# controller.net
KiCad netlist of a schematic drawn in EAGLE
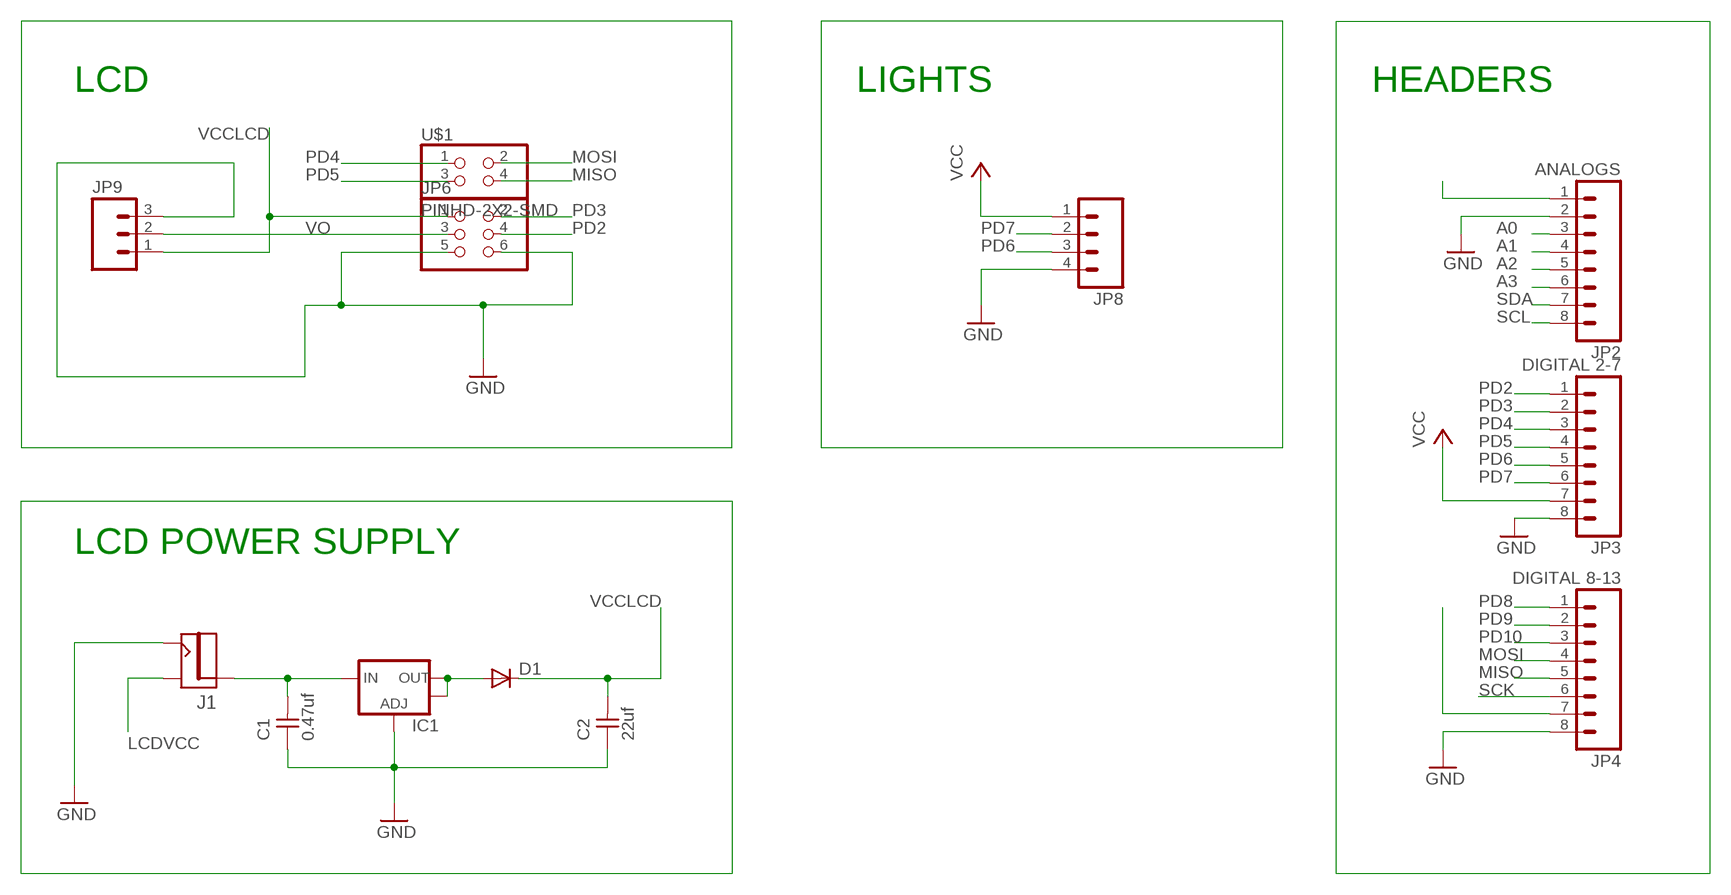
[diagram p0: schematic, sheet 1]

(export (version "E")
  (design (tool "Eeschema 10.0.6"))
  (components
    (comp (ref "C1")
      (value "0.47uf")
      (footprint "eagle-import:1206")
      (libsource (lib "eagle-import") (part "UNPOLARIZED_CAPACITOR1206"))
    )
    (comp (ref "C2")
      (value "22uf")
      (footprint "eagle-import:1206")
      (libsource (lib "eagle-import") (part "UNPOLARIZED_CAPACITOR1206"))
    )
    (comp (ref "D1")
      (value "DIODESOD123")
      (footprint "eagle-import:SOD123")
      (libsource (lib "eagle-import") (part "DIODESOD123"))
    )
    (comp (ref "IC1")
      (value "V_REG_LM1117SOT223")
      (footprint "eagle-import:SOT223")
      (libsource (lib "eagle-import") (part "V_REG_LM1117SOT223"))
    )
    (comp (ref "J1")
      (value "JACK.65MM")
      (footprint "eagle-import:JACK_.65MM")
      (libsource (lib "eagle-import") (part "JACK.65MM"))
    )
    (comp (ref "JP2")
      (value "ANALOGS")
      (footprint "eagle-import:1X08")
      (libsource (lib "eagle-import") (part "M08"))
    )
    (comp (ref "JP3")
      (value "DIGITAL 2-7")
      (footprint "eagle-import:1X08")
      (libsource (lib "eagle-import") (part "M08"))
    )
    (comp (ref "JP4")
      (value "DIGITAL 8-13")
      (footprint "eagle-import:1X08")
      (libsource (lib "eagle-import") (part "M08"))
    )
    (comp (ref "JP6")
      (value "PINHD-2X3-SMD")
      (footprint "eagle-import:2X03SMD")
      (libsource (lib "eagle-import") (part "PINHD-2X3-SMD"))
    )
    (comp (ref "JP8")
      (value "M04PTH")
      (footprint "eagle-import:1X04")
      (libsource (lib "eagle-import") (part "M04PTH"))
    )
    (comp (ref "JP9")
      (value "M03PTH")
      (footprint "eagle-import:1X03")
      (libsource (lib "eagle-import") (part "M03PTH"))
    )
    (comp (ref "U$1")
      (value "PINHD-2X2-SMD")
      (footprint "eagle-import:2X02SMD")
      (libsource (lib "eagle-import") (part "PINHD-2X2-SMD"))
    )
  )
  (nets
    (net (code "1") (name "/A0") (class "Default")
      (node (ref "JP2") (pin "3") (pinfunction "3_3") (pintype "passive"))
    )
    (net (code "2") (name "/A1") (class "Default")
      (node (ref "JP2") (pin "4") (pinfunction "4_4") (pintype "passive"))
    )
    (net (code "3") (name "/A2") (class "Default")
      (node (ref "JP2") (pin "5") (pinfunction "5_5") (pintype "passive"))
    )
    (net (code "4") (name "/A3") (class "Default")
      (node (ref "JP2") (pin "6") (pinfunction "6_6") (pintype "passive"))
    )
    (net (code "5") (name "/LCDVCC") (class "Default")
      (node (ref "J1") (pin "CONTACT") (pinfunction "SHUNT_CONTACT") (pintype "bidirectional"))
    )
    (net (code "6") (name "/MISO") (class "Default")
      (node (ref "JP4") (pin "5") (pinfunction "5_5") (pintype "passive"))
      (node (ref "U$1") (pin "4") (pinfunction "4_4") (pintype "passive"))
    )
    (net (code "7") (name "/MOSI") (class "Default")
      (node (ref "JP4") (pin "4") (pinfunction "4_4") (pintype "passive"))
      (node (ref "U$1") (pin "2") (pinfunction "2_2") (pintype "passive"))
    )
    (net (code "8") (name "/PD2") (class "Default")
      (node (ref "JP3") (pin "1") (pinfunction "1_1") (pintype "passive"))
      (node (ref "JP6") (pin "4") (pinfunction "4_4") (pintype "passive"))
    )
    (net (code "9") (name "/PD3") (class "Default")
      (node (ref "JP3") (pin "2") (pinfunction "2_2") (pintype "passive"))
      (node (ref "JP6") (pin "2") (pinfunction "2_2") (pintype "passive"))
    )
    (net (code "10") (name "/PD4") (class "Default")
      (node (ref "JP3") (pin "3") (pinfunction "3_3") (pintype "passive"))
      (node (ref "U$1") (pin "1") (pinfunction "1_1") (pintype "passive"))
    )
    (net (code "11") (name "/PD5") (class "Default")
      (node (ref "JP3") (pin "4") (pinfunction "4_4") (pintype "passive"))
      (node (ref "U$1") (pin "3") (pinfunction "3_3") (pintype "passive"))
    )
    (net (code "12") (name "/PD6") (class "Default")
      (node (ref "JP3") (pin "5") (pinfunction "5_5") (pintype "passive"))
      (node (ref "JP8") (pin "3") (pinfunction "3_3") (pintype "passive"))
    )
    (net (code "13") (name "/PD7") (class "Default")
      (node (ref "JP3") (pin "6") (pinfunction "6_6") (pintype "passive"))
      (node (ref "JP8") (pin "2") (pinfunction "2_2") (pintype "passive"))
    )
    (net (code "14") (name "/PD8") (class "Default")
      (node (ref "JP4") (pin "1") (pinfunction "1_1") (pintype "passive"))
    )
    (net (code "15") (name "/PD9") (class "Default")
      (node (ref "JP4") (pin "2") (pinfunction "2_2") (pintype "passive"))
    )
    (net (code "16") (name "/PD10") (class "Default")
      (node (ref "JP4") (pin "3") (pinfunction "3_3") (pintype "passive"))
    )
    (net (code "17") (name "/SCK") (class "Default")
      (node (ref "JP4") (pin "6") (pinfunction "6_6") (pintype "passive"))
    )
    (net (code "18") (name "/SCL") (class "Default")
      (node (ref "JP2") (pin "8") (pinfunction "8_8") (pintype "passive"))
    )
    (net (code "19") (name "/SDA") (class "Default")
      (node (ref "JP2") (pin "7") (pinfunction "7_7") (pintype "passive"))
    )
    (net (code "20") (name "/VCCLCD") (class "Default")
      (node (ref "C2") (pin "2") (pinfunction "2_2") (pintype "passive"))
      (node (ref "D1") (pin "CATHODE") (pinfunction "C_CATHODE") (pintype "passive"))
      (node (ref "JP6") (pin "1") (pinfunction "1_1") (pintype "passive"))
      (node (ref "JP9") (pin "1") (pinfunction "1_1") (pintype "passive"))
    )
    (net (code "21") (name "/VO") (class "Default")
      (node (ref "JP6") (pin "3") (pinfunction "3_3") (pintype "passive"))
      (node (ref "JP9") (pin "2") (pinfunction "2_2") (pintype "passive"))
    )
    (net (code "22") (name "GND") (class "Default")
      (node (ref "C1") (pin "1") (pinfunction "1_1") (pintype "passive"))
      (node (ref "C2") (pin "1") (pinfunction "1_1") (pintype "passive"))
      (node (ref "IC1") (pin "1") (pinfunction "ADJ_1") (pintype "input"))
      (node (ref "J1") (pin "SHUNT") (pinfunction "CONTACT_SHUNT") (pintype "bidirectional"))
      (node (ref "JP2") (pin "2") (pinfunction "2_2") (pintype "passive"))
      (node (ref "JP3") (pin "8") (pinfunction "8_8") (pintype "passive"))
      (node (ref "JP4") (pin "8") (pinfunction "8_8") (pintype "passive"))
      (node (ref "JP6") (pin "5") (pinfunction "5_5") (pintype "passive"))
      (node (ref "JP6") (pin "6") (pinfunction "6_6") (pintype "passive"))
      (node (ref "JP8") (pin "4") (pinfunction "4_4") (pintype "passive"))
      (node (ref "JP9") (pin "3") (pinfunction "3_3") (pintype "passive"))
    )
    (net (code "23") (name "Net-(D1-A)") (class "Default")
      (node (ref "D1") (pin "ANODE") (pinfunction "A_ANODE") (pintype "passive"))
      (node (ref "IC1") (pin "2") (pinfunction "OUT_2") (pintype "output"))
      (node (ref "IC1") (pin "4") (pinfunction "OUT_4") (pintype "output"))
    )
    (net (code "24") (name "Net-(IC1-IN)") (class "Default")
      (node (ref "C1") (pin "2") (pinfunction "2_2") (pintype "passive"))
      (node (ref "IC1") (pin "3") (pinfunction "IN_3") (pintype "input"))
      (node (ref "J1") (pin "PIN") (pinfunction "PIN_PIN") (pintype "bidirectional"))
    )
    (net (code "25") (name "VCC") (class "Default")
      (node (ref "JP3") (pin "7") (pinfunction "7_7") (pintype "passive"))
      (node (ref "JP8") (pin "1") (pinfunction "1_1") (pintype "passive"))
    )
    (net (code "26") (name "unconnected-(JP2-Pad1)") (class "Default")
      (node (ref "JP2") (pin "1") (pinfunction "1_1") (pintype "passive"))
    )
    (net (code "27") (name "unconnected-(JP4-Pad7)") (class "Default")
      (node (ref "JP4") (pin "7") (pinfunction "7_7") (pintype "passive"))
    )
  )
)
